# glowproxy_alpha.net
KiCad netlist of a schematic drawn in EAGLE
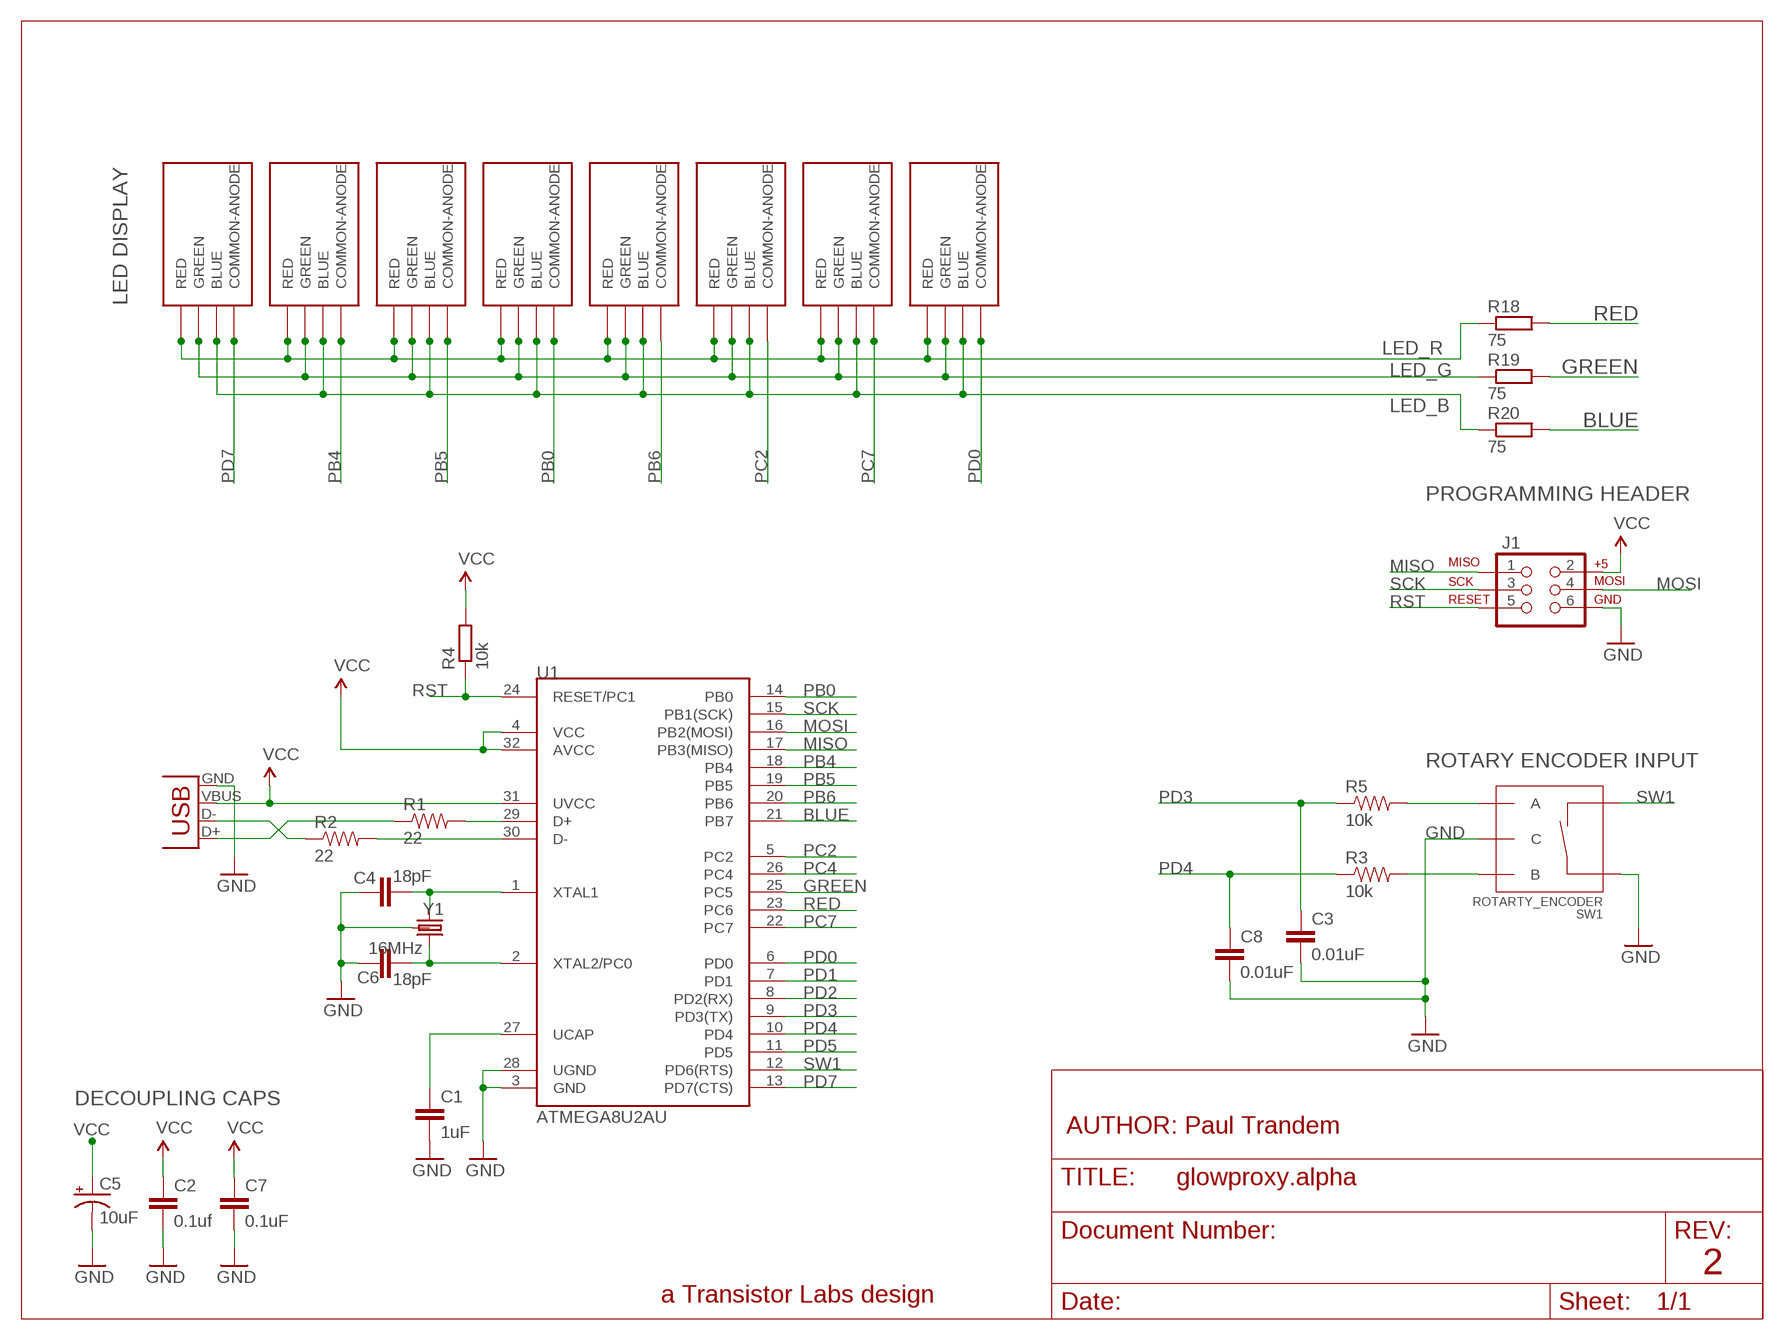
[diagram p0: schematic, sheet 1]

(export (version "E")
  (design (tool "Eeschema 10.0.6"))
  (components
    (comp (ref "C1")
      (value "1uF")
      (footprint "eagle-import:C0603")
      (libsource (lib "eagle-import") (part "C-EUC0603"))
    )
    (comp (ref "C2")
      (value "0.1uf")
      (footprint "eagle-import:C0603")
      (libsource (lib "eagle-import") (part "C-EUC0603"))
    )
    (comp (ref "C3")
      (value "0.01uF")
      (footprint "eagle-import:C0603")
      (libsource (lib "eagle-import") (part "C-EUC0603"))
    )
    (comp (ref "C4")
      (value "18pF")
      (footprint "eagle-import:0603-CAP")
      (libsource (lib "eagle-import") (part "CAP0603-CAP"))
    )
    (comp (ref "C5")
      (value "10uF")
      (footprint "eagle-import:EIA3216")
      (libsource (lib "eagle-import") (part "CAP_POL1206"))
    )
    (comp (ref "C6")
      (value "18pF")
      (footprint "eagle-import:0603-CAP")
      (libsource (lib "eagle-import") (part "CAP0603-CAP"))
    )
    (comp (ref "C7")
      (value "0.1uF")
      (footprint "eagle-import:C0603")
      (libsource (lib "eagle-import") (part "C-EUC0603"))
    )
    (comp (ref "C8")
      (value "0.01uF")
      (footprint "eagle-import:C0603")
      (libsource (lib "eagle-import") (part "C-EUC0603"))
    )
    (comp (ref "J1")
      (value "AVR_SPI_PRG_6PTH")
      (footprint "eagle-import:2X3")
      (libsource (lib "eagle-import") (part "AVR_SPI_PRG_6PTH"))
    )
    (comp (ref "LED0")
      (value "RGB-LED-SMD-CLV1A-FKB")
      (footprint "eagle-import:RGB-LED-SMD-CLV1A-FKB")
      (libsource (lib "eagle-import") (part "RGB-LED-SMD-CLV1A-FKB"))
    )
    (comp (ref "LED1")
      (value "RGB-LED-SMD-CLV1A-FKB")
      (footprint "eagle-import:RGB-LED-SMD-CLV1A-FKB")
      (libsource (lib "eagle-import") (part "RGB-LED-SMD-CLV1A-FKB"))
    )
    (comp (ref "LED2")
      (value "RGB-LED-SMD-CLV1A-FKB")
      (footprint "eagle-import:RGB-LED-SMD-CLV1A-FKB")
      (libsource (lib "eagle-import") (part "RGB-LED-SMD-CLV1A-FKB"))
    )
    (comp (ref "LED3")
      (value "RGB-LED-SMD-CLV1A-FKB")
      (footprint "eagle-import:RGB-LED-SMD-CLV1A-FKB")
      (libsource (lib "eagle-import") (part "RGB-LED-SMD-CLV1A-FKB"))
    )
    (comp (ref "LED4")
      (value "RGB-LED-SMD-CLV1A-FKB")
      (footprint "eagle-import:RGB-LED-SMD-CLV1A-FKB")
      (libsource (lib "eagle-import") (part "RGB-LED-SMD-CLV1A-FKB"))
    )
    (comp (ref "LED5")
      (value "RGB-LED-SMD-CLV1A-FKB")
      (footprint "eagle-import:RGB-LED-SMD-CLV1A-FKB")
      (libsource (lib "eagle-import") (part "RGB-LED-SMD-CLV1A-FKB"))
    )
    (comp (ref "LED6")
      (value "RGB-LED-SMD-CLV1A-FKB")
      (footprint "eagle-import:RGB-LED-SMD-CLV1A-FKB")
      (libsource (lib "eagle-import") (part "RGB-LED-SMD-CLV1A-FKB"))
    )
    (comp (ref "LED7")
      (value "RGB-LED-SMD-CLV1A-FKB")
      (footprint "eagle-import:RGB-LED-SMD-CLV1A-FKB")
      (libsource (lib "eagle-import") (part "RGB-LED-SMD-CLV1A-FKB"))
    )
    (comp (ref "R1")
      (value "22")
      (footprint "eagle-import:0603-RES")
      (libsource (lib "eagle-import") (part "RESISTOR0603-RES"))
    )
    (comp (ref "R2")
      (value "22")
      (footprint "eagle-import:0603-RES")
      (libsource (lib "eagle-import") (part "RESISTOR0603-RES"))
    )
    (comp (ref "R3")
      (value "10k")
      (footprint "eagle-import:0603-RES")
      (libsource (lib "eagle-import") (part "RESISTOR0603-RES"))
    )
    (comp (ref "R4")
      (value "10k")
      (footprint "eagle-import:R0603")
      (libsource (lib "eagle-import") (part "R-EU_R0603"))
    )
    (comp (ref "R5")
      (value "10k")
      (footprint "eagle-import:0603-RES")
      (libsource (lib "eagle-import") (part "RESISTOR0603-RES"))
    )
    (comp (ref "R18")
      (value "75")
      (footprint "eagle-import:R0603")
      (libsource (lib "eagle-import") (part "R-EU_R0603"))
    )
    (comp (ref "R19")
      (value "75")
      (footprint "eagle-import:R0603")
      (libsource (lib "eagle-import") (part "R-EU_R0603"))
    )
    (comp (ref "R20")
      (value "75")
      (footprint "eagle-import:R0603")
      (libsource (lib "eagle-import") (part "R-EU_R0603"))
    )
    (comp (ref "SW1")
      (value "ROTARTY_ENCODER")
      (footprint "eagle-import:ROTARY_ENC_PLAIN")
      (libsource (lib "eagle-import") (part "ROTARTY_ENCODER"))
    )
    (comp (ref "U1")
      (value "ATMEGA8U2AU")
      (footprint "eagle-import:TQFP32-08")
      (libsource (lib "eagle-import") (part "ATMEGA8U2AU"))
    )
    (comp (ref "X1")
      (value "USBSMD")
      (footprint "eagle-import:USB-MINIB")
      (libsource (lib "eagle-import") (part "USBSMD"))
    )
    (comp (ref "Y1")
      (value "16MHz")
      (footprint "eagle-import:CRYSTAL-SMD-5X3")
      (libsource (lib "eagle-import") (part "CRYSTAL5X3"))
    )
  )
  (nets
    (net (code "1") (name "/BLUE") (class "Default")
      (node (ref "R20") (pin "2") (pinfunction "2_2") (pintype "passive"))
      (node (ref "U1") (pin "21") (pinfunction "PB7_21") (pintype "bidirectional"))
    )
    (net (code "2") (name "/GREEN") (class "Default")
      (node (ref "R19") (pin "2") (pinfunction "2_2") (pintype "passive"))
      (node (ref "U1") (pin "25") (pinfunction "PC5_25") (pintype "bidirectional"))
    )
    (net (code "3") (name "/LED_B") (class "Default")
      (node (ref "LED0") (pin "BLUE") (pinfunction "BLUE_BLUE") (pintype "bidirectional"))
      (node (ref "LED1") (pin "BLUE") (pinfunction "BLUE_BLUE") (pintype "bidirectional"))
      (node (ref "LED2") (pin "BLUE") (pinfunction "BLUE_BLUE") (pintype "bidirectional"))
      (node (ref "LED3") (pin "BLUE") (pinfunction "BLUE_BLUE") (pintype "bidirectional"))
      (node (ref "LED4") (pin "BLUE") (pinfunction "BLUE_BLUE") (pintype "bidirectional"))
      (node (ref "LED5") (pin "BLUE") (pinfunction "BLUE_BLUE") (pintype "bidirectional"))
      (node (ref "LED6") (pin "BLUE") (pinfunction "BLUE_BLUE") (pintype "bidirectional"))
      (node (ref "LED7") (pin "BLUE") (pinfunction "BLUE_BLUE") (pintype "bidirectional"))
      (node (ref "R20") (pin "1") (pinfunction "1_1") (pintype "passive"))
    )
    (net (code "4") (name "/LED_G") (class "Default")
      (node (ref "LED0") (pin "GREEN") (pinfunction "GREEN_GREEN") (pintype "bidirectional"))
      (node (ref "LED1") (pin "GREEN") (pinfunction "GREEN_GREEN") (pintype "bidirectional"))
      (node (ref "LED2") (pin "GREEN") (pinfunction "GREEN_GREEN") (pintype "bidirectional"))
      (node (ref "LED3") (pin "GREEN") (pinfunction "GREEN_GREEN") (pintype "bidirectional"))
      (node (ref "LED4") (pin "GREEN") (pinfunction "GREEN_GREEN") (pintype "bidirectional"))
      (node (ref "LED5") (pin "GREEN") (pinfunction "GREEN_GREEN") (pintype "bidirectional"))
      (node (ref "LED6") (pin "GREEN") (pinfunction "GREEN_GREEN") (pintype "bidirectional"))
      (node (ref "LED7") (pin "GREEN") (pinfunction "GREEN_GREEN") (pintype "bidirectional"))
      (node (ref "R19") (pin "1") (pinfunction "1_1") (pintype "passive"))
    )
    (net (code "5") (name "/LED_R") (class "Default")
      (node (ref "LED0") (pin "RED") (pinfunction "RED_RED") (pintype "bidirectional"))
      (node (ref "LED1") (pin "RED") (pinfunction "RED_RED") (pintype "bidirectional"))
      (node (ref "LED2") (pin "RED") (pinfunction "RED_RED") (pintype "bidirectional"))
      (node (ref "LED3") (pin "RED") (pinfunction "RED_RED") (pintype "bidirectional"))
      (node (ref "LED4") (pin "RED") (pinfunction "RED_RED") (pintype "bidirectional"))
      (node (ref "LED5") (pin "RED") (pinfunction "RED_RED") (pintype "bidirectional"))
      (node (ref "LED6") (pin "RED") (pinfunction "RED_RED") (pintype "bidirectional"))
      (node (ref "LED7") (pin "RED") (pinfunction "RED_RED") (pintype "bidirectional"))
      (node (ref "R18") (pin "1") (pinfunction "1_1") (pintype "passive"))
    )
    (net (code "6") (name "/MISO") (class "Default")
      (node (ref "J1") (pin "1") (pinfunction "1_1") (pintype "passive"))
      (node (ref "U1") (pin "17") (pinfunction "PB3(MISO)_17") (pintype "bidirectional"))
    )
    (net (code "7") (name "/MOSI") (class "Default")
      (node (ref "J1") (pin "4") (pinfunction "4_4") (pintype "passive"))
      (node (ref "U1") (pin "16") (pinfunction "PB2(MOSI)_16") (pintype "bidirectional"))
    )
    (net (code "8") (name "/PB0") (class "Default")
      (node (ref "LED4") (pin "COMMON-ANODE") (pinfunction "COMMON-ANODE_COMMON-ANODE") (pintype "bidirectional"))
      (node (ref "U1") (pin "14") (pinfunction "PB0_14") (pintype "bidirectional"))
    )
    (net (code "9") (name "/PB4") (class "Default")
      (node (ref "LED0") (pin "COMMON-ANODE") (pinfunction "COMMON-ANODE_COMMON-ANODE") (pintype "bidirectional"))
      (node (ref "U1") (pin "18") (pinfunction "PB4_18") (pintype "bidirectional"))
    )
    (net (code "10") (name "/PB5") (class "Default")
      (node (ref "LED7") (pin "COMMON-ANODE") (pinfunction "COMMON-ANODE_COMMON-ANODE") (pintype "bidirectional"))
      (node (ref "U1") (pin "19") (pinfunction "PB5_19") (pintype "bidirectional"))
    )
    (net (code "11") (name "/PB6") (class "Default")
      (node (ref "LED5") (pin "COMMON-ANODE") (pinfunction "COMMON-ANODE_COMMON-ANODE") (pintype "bidirectional"))
      (node (ref "U1") (pin "20") (pinfunction "PB6_20") (pintype "bidirectional"))
    )
    (net (code "12") (name "/PC2") (class "Default")
      (node (ref "LED1") (pin "COMMON-ANODE") (pinfunction "COMMON-ANODE_COMMON-ANODE") (pintype "bidirectional"))
      (node (ref "U1") (pin "5") (pinfunction "PC2_5") (pintype "bidirectional"))
    )
    (net (code "13") (name "/PC4") (class "Default")
      (node (ref "U1") (pin "26") (pinfunction "PC4_26") (pintype "bidirectional"))
    )
    (net (code "14") (name "/PC7") (class "Default")
      (node (ref "LED6") (pin "COMMON-ANODE") (pinfunction "COMMON-ANODE_COMMON-ANODE") (pintype "bidirectional"))
      (node (ref "U1") (pin "22") (pinfunction "PC7_22") (pintype "bidirectional"))
    )
    (net (code "15") (name "/PD0") (class "Default")
      (node (ref "LED2") (pin "COMMON-ANODE") (pinfunction "COMMON-ANODE_COMMON-ANODE") (pintype "bidirectional"))
      (node (ref "U1") (pin "6") (pinfunction "PD0_6") (pintype "bidirectional"))
    )
    (net (code "16") (name "/PD1") (class "Default")
      (node (ref "U1") (pin "7") (pinfunction "PD1_7") (pintype "bidirectional"))
    )
    (net (code "17") (name "/PD2") (class "Default")
      (node (ref "U1") (pin "8") (pinfunction "PD2(RX)_8") (pintype "bidirectional"))
    )
    (net (code "18") (name "/PD3") (class "Default")
      (node (ref "C3") (pin "1") (pinfunction "1_1") (pintype "passive"))
      (node (ref "R5") (pin "1") (pinfunction "1_1") (pintype "passive"))
      (node (ref "U1") (pin "9") (pinfunction "PD3(TX)_9") (pintype "bidirectional"))
    )
    (net (code "19") (name "/PD4") (class "Default")
      (node (ref "C8") (pin "1") (pinfunction "1_1") (pintype "passive"))
      (node (ref "R3") (pin "1") (pinfunction "1_1") (pintype "passive"))
      (node (ref "U1") (pin "10") (pinfunction "PD4_10") (pintype "bidirectional"))
    )
    (net (code "20") (name "/PD5") (class "Default")
      (node (ref "U1") (pin "11") (pinfunction "PD5_11") (pintype "bidirectional"))
    )
    (net (code "21") (name "/PD7") (class "Default")
      (node (ref "LED3") (pin "COMMON-ANODE") (pinfunction "COMMON-ANODE_COMMON-ANODE") (pintype "bidirectional"))
      (node (ref "U1") (pin "13") (pinfunction "PD7(CTS)_13") (pintype "bidirectional"))
    )
    (net (code "22") (name "/RED") (class "Default")
      (node (ref "R18") (pin "2") (pinfunction "2_2") (pintype "passive"))
      (node (ref "U1") (pin "23") (pinfunction "PC6_23") (pintype "bidirectional"))
    )
    (net (code "23") (name "/RST") (class "Default")
      (node (ref "J1") (pin "5") (pinfunction "5_5") (pintype "passive"))
      (node (ref "R4") (pin "1") (pinfunction "1_1") (pintype "passive"))
      (node (ref "U1") (pin "24") (pinfunction "RESET/PC1_24") (pintype "bidirectional"))
    )
    (net (code "24") (name "/SCK") (class "Default")
      (node (ref "J1") (pin "3") (pinfunction "3_3") (pintype "passive"))
      (node (ref "U1") (pin "15") (pinfunction "PB1(SCK)_15") (pintype "bidirectional"))
    )
    (net (code "25") (name "/SW1") (class "Default")
      (node (ref "SW1") (pin "SW-") (pinfunction "SW-_SW-") (pintype "bidirectional"))
      (node (ref "U1") (pin "12") (pinfunction "PD6(RTS)_12") (pintype "bidirectional"))
    )
    (net (code "26") (name "GND") (class "Default")
      (node (ref "C1") (pin "2") (pinfunction "2_2") (pintype "passive"))
      (node (ref "C2") (pin "2") (pinfunction "2_2") (pintype "passive"))
      (node (ref "C3") (pin "2") (pinfunction "2_2") (pintype "passive"))
      (node (ref "C4") (pin "2") (pinfunction "2_2") (pintype "passive"))
      (node (ref "C5") (pin "C") (pinfunction "-_C") (pintype "passive"))
      (node (ref "C6") (pin "2") (pinfunction "2_2") (pintype "passive"))
      (node (ref "C7") (pin "2") (pinfunction "2_2") (pintype "passive"))
      (node (ref "C8") (pin "2") (pinfunction "2_2") (pintype "passive"))
      (node (ref "J1") (pin "6") (pinfunction "6_6") (pintype "passive"))
      (node (ref "SW1") (pin "C") (pinfunction "C_C") (pintype "bidirectional"))
      (node (ref "SW1") (pin "SW+") (pinfunction "SW+_SW+") (pintype "bidirectional"))
      (node (ref "U1") (pin "28") (pinfunction "UGND_28") (pintype "bidirectional"))
      (node (ref "U1") (pin "3") (pinfunction "GND_3") (pintype "bidirectional"))
      (node (ref "X1") (pin "GND") (pinfunction "GND_GND") (pintype "bidirectional"))
      (node (ref "Y1") (pin "2") (pinfunction "GND_2") (pintype "power_in"))
      (node (ref "Y1") (pin "4") (pinfunction "GND_4") (pintype "power_in"))
    )
    (net (code "27") (name "Net-(R1-Pad1)") (class "Default")
      (node (ref "R1") (pin "1") (pinfunction "1_1") (pintype "passive"))
      (node (ref "X1") (pin "D+") (pinfunction "D+_D+") (pintype "bidirectional"))
    )
    (net (code "28") (name "Net-(R2-Pad1)") (class "Default")
      (node (ref "R2") (pin "1") (pinfunction "1_1") (pintype "passive"))
      (node (ref "X1") (pin "D-") (pinfunction "D-_D-") (pintype "bidirectional"))
    )
    (net (code "29") (name "Net-(R3-Pad2)") (class "Default")
      (node (ref "R3") (pin "2") (pinfunction "2_2") (pintype "passive"))
      (node (ref "SW1") (pin "B") (pinfunction "B_B") (pintype "bidirectional"))
    )
    (net (code "30") (name "Net-(R5-Pad2)") (class "Default")
      (node (ref "R5") (pin "2") (pinfunction "2_2") (pintype "passive"))
      (node (ref "SW1") (pin "A") (pinfunction "A_A") (pintype "bidirectional"))
    )
    (net (code "31") (name "Net-(U1-D+)") (class "Default")
      (node (ref "R1") (pin "2") (pinfunction "2_2") (pintype "passive"))
      (node (ref "U1") (pin "29") (pinfunction "D+_29") (pintype "bidirectional"))
    )
    (net (code "32") (name "Net-(U1-D-)") (class "Default")
      (node (ref "R2") (pin "2") (pinfunction "2_2") (pintype "passive"))
      (node (ref "U1") (pin "30") (pinfunction "D-_30") (pintype "bidirectional"))
    )
    (net (code "33") (name "Net-(U1-UCAP)") (class "Default")
      (node (ref "C1") (pin "1") (pinfunction "1_1") (pintype "passive"))
      (node (ref "U1") (pin "27") (pinfunction "UCAP_27") (pintype "bidirectional"))
    )
    (net (code "34") (name "Net-(U1-XTAL1)") (class "Default")
      (node (ref "C4") (pin "1") (pinfunction "1_1") (pintype "passive"))
      (node (ref "U1") (pin "1") (pinfunction "XTAL1_1") (pintype "bidirectional"))
      (node (ref "Y1") (pin "3") (pinfunction "2_3") (pintype "passive"))
    )
    (net (code "35") (name "Net-(U1-XTAL2{slash}PC0)") (class "Default")
      (node (ref "C6") (pin "1") (pinfunction "1_1") (pintype "passive"))
      (node (ref "U1") (pin "2") (pinfunction "XTAL2/PC0_2") (pintype "bidirectional"))
      (node (ref "Y1") (pin "1") (pinfunction "1_1") (pintype "passive"))
    )
    (net (code "36") (name "VCC") (class "Default")
      (node (ref "C2") (pin "1") (pinfunction "1_1") (pintype "passive"))
      (node (ref "C5") (pin "A") (pinfunction "+_A") (pintype "passive"))
      (node (ref "C7") (pin "1") (pinfunction "1_1") (pintype "passive"))
      (node (ref "J1") (pin "2") (pinfunction "2_2") (pintype "passive"))
      (node (ref "R4") (pin "2") (pinfunction "2_2") (pintype "passive"))
      (node (ref "U1") (pin "31") (pinfunction "UVCC_31") (pintype "bidirectional"))
      (node (ref "U1") (pin "32") (pinfunction "AVCC_32") (pintype "bidirectional"))
      (node (ref "U1") (pin "4") (pinfunction "VCC_4") (pintype "bidirectional"))
      (node (ref "X1") (pin "VBUS") (pinfunction "VBUS_VBUS") (pintype "bidirectional"))
    )
  )
)
